# vref_low_current_20_vpp_source_v01.net
KiCad netlist of a schematic drawn in EAGLE
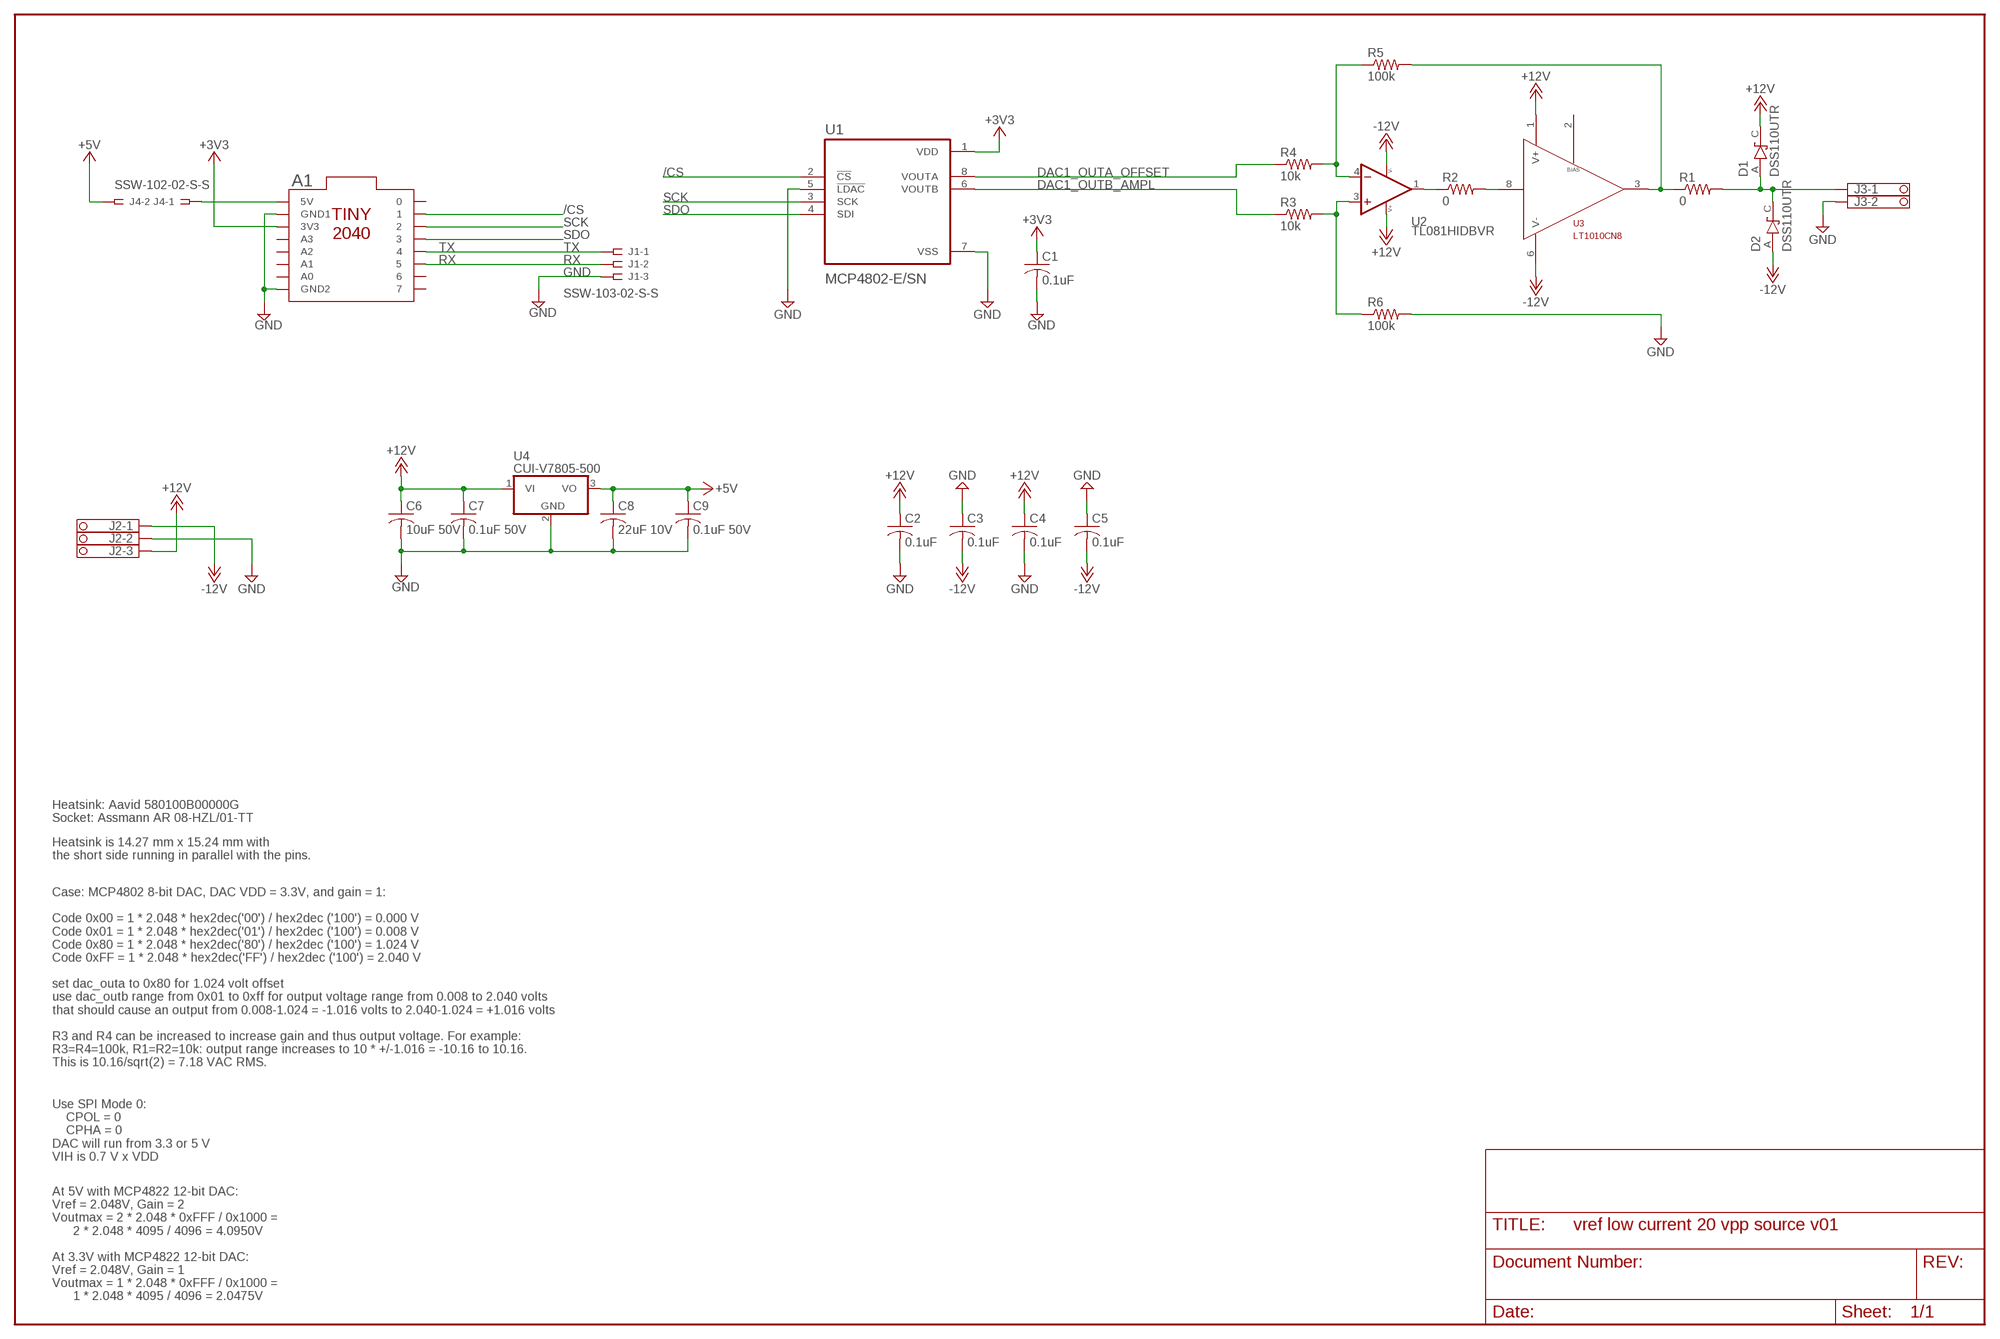
[diagram p0: schematic, sheet 1]

(export (version "E")
  (design (tool "Eeschema 10.0.6"))
  (components
    (comp (ref "A1")
      (value "TINY2040PTHLOCK")
      (footprint "eagle-import:TINY2040_PTH_LOCK")
      (libsource (lib "eagle-import") (part "TINY2040PTHLOCK"))
    )
    (comp (ref "C1")
      (value "0.1uF")
      (footprint "eagle-import:C0603K")
      (fields (field (name "MFR") "KEMET") (field (name "MFR_PART_NO") "C1206C104K5RACAUTO"))
      (libsource (lib "eagle-import") (part "C-USC0603K"))
    )
    (comp (ref "C2")
      (value "0.1uF")
      (footprint "eagle-import:C0603K")
      (fields (field (name "MFR") "KEMET") (field (name "MFR_PART_NO") "C1206C104K5RACAUTO"))
      (libsource (lib "eagle-import") (part "C-USC0603K"))
    )
    (comp (ref "C3")
      (value "0.1uF")
      (footprint "eagle-import:C0603K")
      (fields (field (name "MFR") "KEMET") (field (name "MFR_PART_NO") "C1206C104K5RACAUTO"))
      (libsource (lib "eagle-import") (part "C-USC0603K"))
    )
    (comp (ref "C4")
      (value "0.1uF")
      (footprint "eagle-import:C0603K")
      (fields (field (name "MFR") "KEMET") (field (name "MFR_PART_NO") "C1206C104K5RACAUTO"))
      (libsource (lib "eagle-import") (part "C-USC0603K"))
    )
    (comp (ref "C5")
      (value "0.1uF")
      (footprint "eagle-import:C0603K")
      (fields (field (name "MFR") "KEMET") (field (name "MFR_PART_NO") "C1206C104K5RACAUTO"))
      (libsource (lib "eagle-import") (part "C-USC0603K"))
    )
    (comp (ref "C6")
      (value "10uF 50V")
      (footprint "eagle-import:C1210K")
      (fields (field (name "MFR") "KEMET") (field (name "MFR_PART_NO") "C1210C106K5RACTU"))
      (libsource (lib "eagle-import") (part "C-USC1210K"))
    )
    (comp (ref "C7")
      (value "0.1uF 50V")
      (footprint "eagle-import:C1206K")
      (fields (field (name "MFR") "KEMET") (field (name "MFR_PART_NO") "C1206S104M5RACTU"))
      (libsource (lib "eagle-import") (part "C-USC1206K"))
    )
    (comp (ref "C8")
      (value "22uF 10V")
      (footprint "eagle-import:C1206K")
      (fields (field (name "MFR") "KEMET") (field (name "MFR_PART_NO") "C1206C226K8RAC7800"))
      (libsource (lib "eagle-import") (part "C-USC1206K"))
    )
    (comp (ref "C9")
      (value "0.1uF 50V")
      (footprint "eagle-import:C1206K")
      (fields (field (name "MFR") "KEMET") (field (name "MFR_PART_NO") "C1206S104M5RACTU"))
      (libsource (lib "eagle-import") (part "C-USC1206K"))
    )
    (comp (ref "D1")
      (value "DSS110UTR")
      (footprint "eagle-import:SODFL3618X110N")
      (fields (field (name "MF") "SMC Diode Solutions"))
      (libsource (lib "eagle-import") (part "DSS110UTR"))
    )
    (comp (ref "D2")
      (value "DSS110UTR")
      (footprint "eagle-import:SODFL3618X110N")
      (fields (field (name "MF") "SMC Diode Solutions"))
      (libsource (lib "eagle-import") (part "DSS110UTR"))
    )
    (comp (ref "J1")
      (value "SSW-103-02-S-S")
      (footprint "eagle-import:SSW-103-02-S-S")
      (libsource (lib "eagle-import") (part "SSW-103-02-S-S"))
    )
    (comp (ref "J2")
      (value "1751251")
      (footprint "eagle-import:1751251")
      (libsource (lib "eagle-import") (part "1751251"))
    )
    (comp (ref "J3")
      (value "1751248")
      (footprint "eagle-import:1751248")
      (libsource (lib "eagle-import") (part "1751248"))
    )
    (comp (ref "J4")
      (value "SSW-102-02-S-S")
      (footprint "eagle-import:SSW-102-02-S-S")
      (libsource (lib "eagle-import") (part "SSW-102-02-S-S"))
    )
    (comp (ref "R1")
      (value "0")
      (footprint "eagle-import:R1206")
      (libsource (lib "eagle-import") (part "R-US_R1206"))
    )
    (comp (ref "R2")
      (value "0")
      (footprint "eagle-import:R1206")
      (libsource (lib "eagle-import") (part "R-US_R1206"))
    )
    (comp (ref "R3")
      (value "10k")
      (footprint "eagle-import:R1206")
      (libsource (lib "eagle-import") (part "R-US_R1206"))
    )
    (comp (ref "R4")
      (value "10k")
      (footprint "eagle-import:R1206")
      (libsource (lib "eagle-import") (part "R-US_R1206"))
    )
    (comp (ref "R5")
      (value "100k")
      (footprint "eagle-import:R1206")
      (libsource (lib "eagle-import") (part "R-US_R1206"))
    )
    (comp (ref "R6")
      (value "100k")
      (footprint "eagle-import:R1206")
      (libsource (lib "eagle-import") (part "R-US_R1206"))
    )
    (comp (ref "U1")
      (value "MCP4802-E/SN")
      (footprint "eagle-import:SOIC127P600X175-8N")
      (fields
        (field (name "DIGI-KEY_PART_NUMBER") "MCP4802-E/SN-ND")
        (field (name "MF") "Microchip Technology")
      )
      (libsource (lib "eagle-import") (part "MCP4802-E/SN"))
    )
    (comp (ref "U2")
      (value "TL081HIDBVR")
      (footprint "eagle-import:SOT-23-5_DBV_TEX")
      (fields (field (name "COPYRIGHT") "Copyright (C) 2022 Ultra Librarian. All rights reserved."))
      (libsource (lib "eagle-import") (part "TL081HIDBVR"))
    )
    (comp (ref "U3")
      (value "LT1010CN8")
      (footprint "eagle-import:DIL08")
      (libsource (lib "eagle-import") (part "LT1010CN8"))
    )
    (comp (ref "U4")
      (value "CUI-V7805-500")
      (footprint "eagle-import:CUI-78XX-500")
      (libsource (lib "eagle-import") (part "CUI-V7803-500"))
    )
  )
  (nets
    (net (code "1") (name "+3V3") (class "Default")
      (node (ref "A1") (pin "3V3") (pinfunction "3V3_3V3") (pintype "bidirectional"))
      (node (ref "C1") (pin "1") (pinfunction "1_1") (pintype "passive"))
      (node (ref "U1") (pin "1") (pinfunction "VDD_1") (pintype "power_in"))
    )
    (net (code "2") (name "+5V") (class "Default")
      (node (ref "C8") (pin "1") (pinfunction "1_1") (pintype "passive"))
      (node (ref "C9") (pin "1") (pinfunction "1_1") (pintype "passive"))
      (node (ref "J4") (pin "2") (pinfunction "1_2") (pintype "passive"))
      (node (ref "U4") (pin "3") (pinfunction "VO_3") (pintype "passive"))
    )
    (net (code "3") (name "+12V") (class "Default")
      (node (ref "C2") (pin "1") (pinfunction "1_1") (pintype "passive"))
      (node (ref "C4") (pin "1") (pinfunction "1_1") (pintype "passive"))
      (node (ref "C6") (pin "1") (pinfunction "1_1") (pintype "passive"))
      (node (ref "C7") (pin "1") (pinfunction "1_1") (pintype "passive"))
      (node (ref "D1") (pin "C") (pinfunction "K_C") (pintype "passive"))
      (node (ref "J2") (pin "3") (pinfunction "K_3") (pintype "passive"))
      (node (ref "U2") (pin "5") (pinfunction "V+_5") (pintype "power_in"))
      (node (ref "U3") (pin "1") (pinfunction "V+_1") (pintype "bidirectional"))
      (node (ref "U4") (pin "1") (pinfunction "VI_1") (pintype "input"))
    )
    (net (code "4") (name "-12V") (class "Default")
      (node (ref "C3") (pin "2") (pinfunction "2_2") (pintype "passive"))
      (node (ref "C5") (pin "2") (pinfunction "2_2") (pintype "passive"))
      (node (ref "D2") (pin "A") (pinfunction "A_A") (pintype "passive"))
      (node (ref "J2") (pin "1") (pinfunction "K_1") (pintype "passive"))
      (node (ref "U2") (pin "2") (pinfunction "V-_2") (pintype "power_in"))
      (node (ref "U3") (pin "6") (pinfunction "V-_6") (pintype "bidirectional"))
    )
    (net (code "5") (name "/DAC1_OUTA_OFFSET") (class "Default")
      (node (ref "R4") (pin "1") (pinfunction "1_1") (pintype "passive"))
      (node (ref "U1") (pin "8") (pinfunction "VOUTA_8") (pintype "output"))
    )
    (net (code "6") (name "/DAC1_OUTB_AMPL") (class "Default")
      (node (ref "R3") (pin "1") (pinfunction "1_1") (pintype "passive"))
      (node (ref "U1") (pin "6") (pinfunction "VOUTB_6") (pintype "output"))
    )
    (net (code "7") (name "/RX") (class "Default")
      (node (ref "A1") (pin "5") (pinfunction "5_5") (pintype "bidirectional"))
      (node (ref "J1") (pin "2") (pinfunction "1_2") (pintype "passive"))
    )
    (net (code "8") (name "/SCK") (class "Default")
      (node (ref "A1") (pin "2") (pinfunction "2_2") (pintype "bidirectional"))
      (node (ref "U1") (pin "3") (pinfunction "SCK_3") (pintype "input"))
    )
    (net (code "9") (name "/SDO") (class "Default")
      (node (ref "A1") (pin "3") (pinfunction "3_3") (pintype "bidirectional"))
      (node (ref "U1") (pin "4") (pinfunction "SDI_4") (pintype "input"))
    )
    (net (code "10") (name "/TX") (class "Default")
      (node (ref "A1") (pin "4") (pinfunction "4_4") (pintype "bidirectional"))
      (node (ref "J1") (pin "1") (pinfunction "1_1") (pintype "passive"))
    )
    (net (code "11") (name "/{slash}CS") (class "Default")
      (node (ref "A1") (pin "1") (pinfunction "1_1") (pintype "bidirectional"))
      (node (ref "U1") (pin "2") (pinfunction "~{CS}_2") (pintype "input"))
    )
    (net (code "12") (name "GND") (class "Default")
      (node (ref "A1") (pin "GND1") (pinfunction "GND1_GND1") (pintype "bidirectional"))
      (node (ref "A1") (pin "GND2") (pinfunction "GND2_GND2") (pintype "bidirectional"))
      (node (ref "C1") (pin "2") (pinfunction "2_2") (pintype "passive"))
      (node (ref "C2") (pin "2") (pinfunction "2_2") (pintype "passive"))
      (node (ref "C3") (pin "1") (pinfunction "1_1") (pintype "passive"))
      (node (ref "C4") (pin "2") (pinfunction "2_2") (pintype "passive"))
      (node (ref "C5") (pin "1") (pinfunction "1_1") (pintype "passive"))
      (node (ref "C6") (pin "2") (pinfunction "2_2") (pintype "passive"))
      (node (ref "C7") (pin "2") (pinfunction "2_2") (pintype "passive"))
      (node (ref "C8") (pin "2") (pinfunction "2_2") (pintype "passive"))
      (node (ref "C9") (pin "2") (pinfunction "2_2") (pintype "passive"))
      (node (ref "J1") (pin "3") (pinfunction "1_3") (pintype "passive"))
      (node (ref "J2") (pin "2") (pinfunction "K_2") (pintype "passive"))
      (node (ref "J3") (pin "2") (pinfunction "K_2") (pintype "passive"))
      (node (ref "R6") (pin "2") (pinfunction "2_2") (pintype "passive"))
      (node (ref "U1") (pin "5") (pinfunction "~{LDAC}_5") (pintype "input"))
      (node (ref "U1") (pin "7") (pinfunction "VSS_7") (pintype "power_in"))
      (node (ref "U4") (pin "2") (pinfunction "GND_2") (pintype "passive"))
    )
    (net (code "13") (name "Net-(A1-Pad5V)") (class "Default")
      (node (ref "A1") (pin "5V") (pinfunction "5V_5V") (pintype "bidirectional"))
      (node (ref "J4") (pin "1") (pinfunction "1_1") (pintype "passive"))
    )
    (net (code "14") (name "Net-(D2-K)") (class "Default")
      (node (ref "D1") (pin "A") (pinfunction "A_A") (pintype "passive"))
      (node (ref "D2") (pin "C") (pinfunction "K_C") (pintype "passive"))
      (node (ref "J3") (pin "1") (pinfunction "K_1") (pintype "passive"))
      (node (ref "R1") (pin "2") (pinfunction "2_2") (pintype "passive"))
    )
    (net (code "15") (name "Net-(U2-IN+)") (class "Default")
      (node (ref "R3") (pin "2") (pinfunction "2_2") (pintype "passive"))
      (node (ref "R6") (pin "1") (pinfunction "1_1") (pintype "passive"))
      (node (ref "U2") (pin "3") (pinfunction "IN+_3") (pintype "input"))
    )
    (net (code "16") (name "Net-(U2-IN-)") (class "Default")
      (node (ref "R4") (pin "2") (pinfunction "2_2") (pintype "passive"))
      (node (ref "R5") (pin "1") (pinfunction "1_1") (pintype "passive"))
      (node (ref "U2") (pin "4") (pinfunction "IN-_4") (pintype "input"))
    )
    (net (code "17") (name "Net-(U2-OUT)") (class "Default")
      (node (ref "R2") (pin "1") (pinfunction "1_1") (pintype "passive"))
      (node (ref "U2") (pin "1") (pinfunction "OUT_1") (pintype "output"))
    )
    (net (code "18") (name "Net-(U3-INPUT)") (class "Default")
      (node (ref "R2") (pin "2") (pinfunction "2_2") (pintype "passive"))
      (node (ref "U3") (pin "8") (pinfunction "INPUT_8") (pintype "bidirectional"))
    )
    (net (code "19") (name "Net-(U3-OUTPUT)") (class "Default")
      (node (ref "R1") (pin "1") (pinfunction "1_1") (pintype "passive"))
      (node (ref "R5") (pin "2") (pinfunction "2_2") (pintype "passive"))
      (node (ref "U3") (pin "3") (pinfunction "OUTPUT_3") (pintype "bidirectional"))
    )
    (net (code "20") (name "unconnected-(A1-Pad0)") (class "Default")
      (node (ref "A1") (pin "0") (pinfunction "0_0") (pintype "bidirectional"))
    )
    (net (code "21") (name "unconnected-(A1-Pad6)") (class "Default")
      (node (ref "A1") (pin "6") (pinfunction "6_6") (pintype "bidirectional"))
    )
    (net (code "22") (name "unconnected-(A1-Pad7)") (class "Default")
      (node (ref "A1") (pin "7") (pinfunction "7_7") (pintype "bidirectional"))
    )
    (net (code "23") (name "unconnected-(A1-PadA0)") (class "Default")
      (node (ref "A1") (pin "A0") (pinfunction "A0_A0") (pintype "bidirectional"))
    )
    (net (code "24") (name "unconnected-(A1-PadA1)") (class "Default")
      (node (ref "A1") (pin "A1") (pinfunction "A1_A1") (pintype "bidirectional"))
    )
    (net (code "25") (name "unconnected-(A1-PadA2)") (class "Default")
      (node (ref "A1") (pin "A2") (pinfunction "A2_A2") (pintype "bidirectional"))
    )
    (net (code "26") (name "unconnected-(A1-PadA3)") (class "Default")
      (node (ref "A1") (pin "A3") (pinfunction "A3_A3") (pintype "bidirectional"))
    )
    (net (code "27") (name "unconnected-(U3-BIAS-Pad2)") (class "Default")
      (node (ref "U3") (pin "2") (pinfunction "BIAS_2") (pintype "bidirectional"))
    )
  )
)
